# LEDLadderSchem.net
KiCad netlist of a schematic drawn in Altium Designer
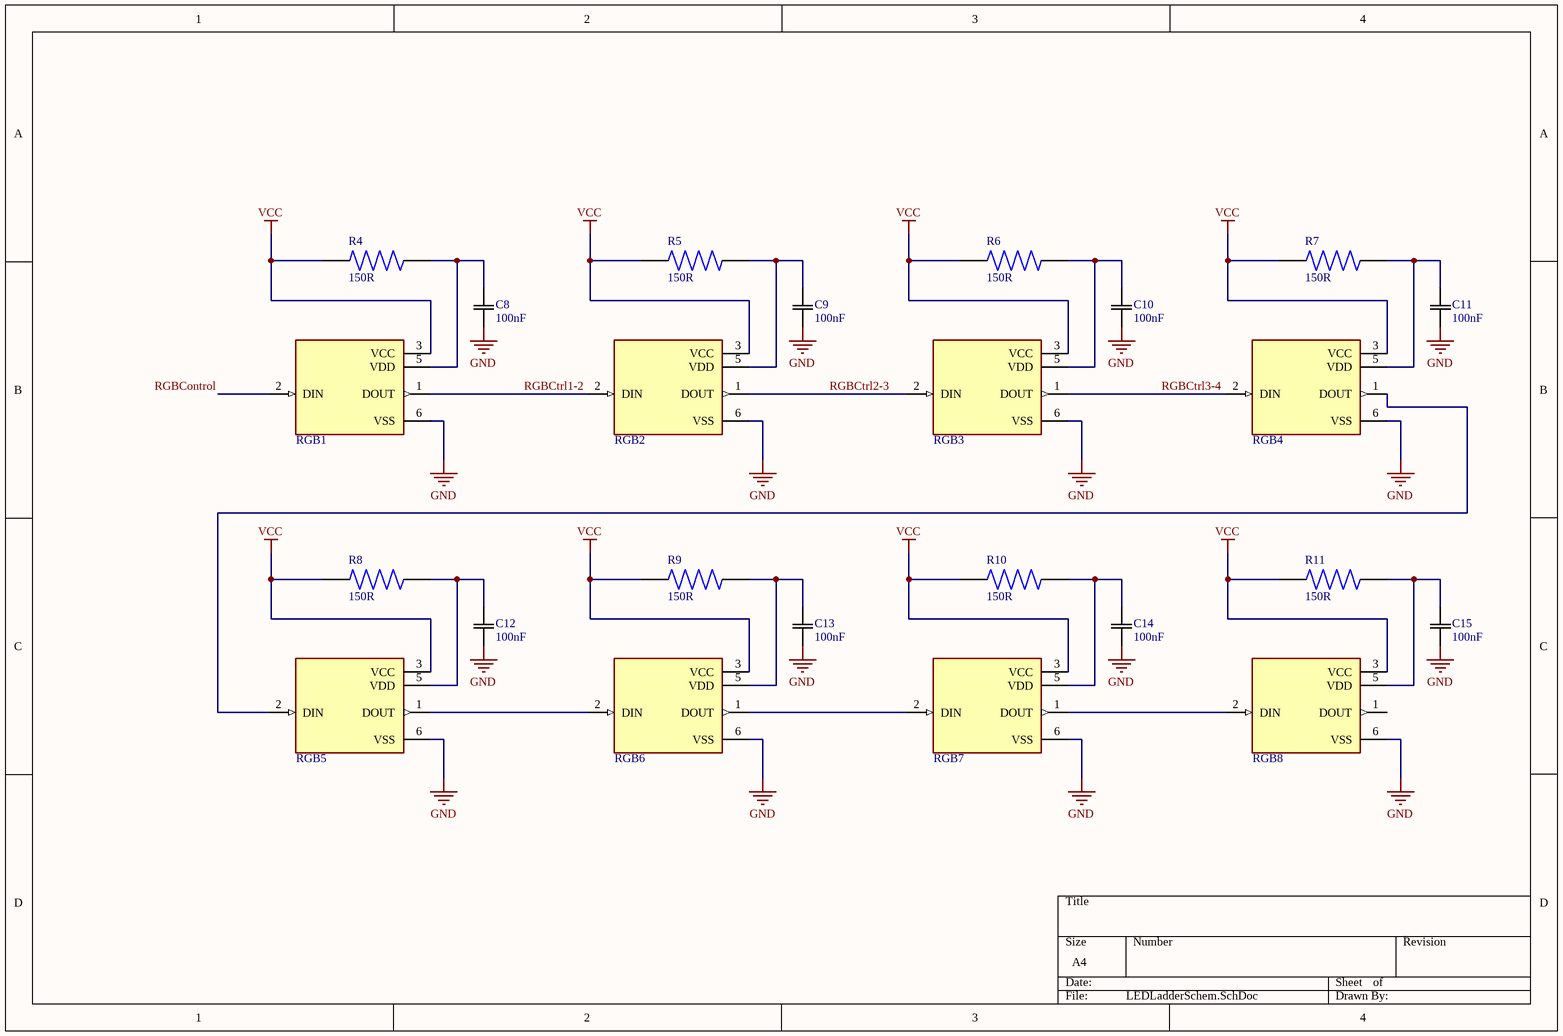
[diagram p0: LEDLadderSchem.SchDoc]

(export (version "E")
  (design (tool "Eeschema 10.0.6"))
  (components
    (comp (ref "C8")
      (value "100nF")
      (footprint "CAPC0603_87N_KEM-M")
      (description "CAP CER 10000PF 50V U2J 0603")
      (fields
        (field (name "MANUFACTURER") "KEMET")
        (field (name "MANUFACTURER PART NUMBER") "C0603C103J5JACTU")
      )
      (libsource (lib "MediaControllerSchLib") (part "C0603C103J5JACTU"))
    )
    (comp (ref "C9")
      (value "100nF")
      (footprint "CAPC0603_87N_KEM-M")
      (description "CAP CER 10000PF 50V U2J 0603")
      (fields
        (field (name "MANUFACTURER") "KEMET")
        (field (name "MANUFACTURER PART NUMBER") "C0603C103J5JACTU")
      )
      (libsource (lib "MediaControllerSchLib") (part "C0603C103J5JACTU"))
    )
    (comp (ref "C10")
      (value "100nF")
      (footprint "CAPC0603_87N_KEM-M")
      (description "CAP CER 10000PF 50V U2J 0603")
      (fields
        (field (name "MANUFACTURER") "KEMET")
        (field (name "MANUFACTURER PART NUMBER") "C0603C103J5JACTU")
      )
      (libsource (lib "MediaControllerSchLib") (part "C0603C103J5JACTU"))
    )
    (comp (ref "C11")
      (value "100nF")
      (footprint "CAPC0603_87N_KEM-M")
      (description "CAP CER 10000PF 50V U2J 0603")
      (fields
        (field (name "MANUFACTURER") "KEMET")
        (field (name "MANUFACTURER PART NUMBER") "C0603C103J5JACTU")
      )
      (libsource (lib "MediaControllerSchLib") (part "C0603C103J5JACTU"))
    )
    (comp (ref "C12")
      (value "100nF")
      (footprint "CAPC0603_87N_KEM-M")
      (description "CAP CER 10000PF 50V U2J 0603")
      (fields
        (field (name "MANUFACTURER") "KEMET")
        (field (name "MANUFACTURER PART NUMBER") "C0603C103J5JACTU")
      )
      (libsource (lib "MediaControllerSchLib") (part "C0603C103J5JACTU"))
    )
    (comp (ref "C13")
      (value "100nF")
      (footprint "CAPC0603_87N_KEM-M")
      (description "CAP CER 10000PF 50V U2J 0603")
      (fields
        (field (name "MANUFACTURER") "KEMET")
        (field (name "MANUFACTURER PART NUMBER") "C0603C103J5JACTU")
      )
      (libsource (lib "MediaControllerSchLib") (part "C0603C103J5JACTU"))
    )
    (comp (ref "C14")
      (value "100nF")
      (footprint "CAPC0603_87N_KEM-M")
      (description "CAP CER 10000PF 50V U2J 0603")
      (fields
        (field (name "MANUFACTURER") "KEMET")
        (field (name "MANUFACTURER PART NUMBER") "C0603C103J5JACTU")
      )
      (libsource (lib "MediaControllerSchLib") (part "C0603C103J5JACTU"))
    )
    (comp (ref "C15")
      (value "100nF")
      (footprint "CAPC0603_87N_KEM-M")
      (description "CAP CER 10000PF 50V U2J 0603")
      (fields
        (field (name "MANUFACTURER") "KEMET")
        (field (name "MANUFACTURER PART NUMBER") "C0603C103J5JACTU")
      )
      (libsource (lib "MediaControllerSchLib") (part "C0603C103J5JACTU"))
    )
    (comp (ref "R4")
      (value "150R")
      (footprint "RES0608_150OHM")
      (description "Res Thick Film 0603 150 Ohm 1% 0.33W(1/3W) ±100ppm/°C Pad SMD Automotive T/R")
      (fields
        (field (name "MANUFACTURER") "Vishay")
        (field (name "MANUFACTURER PART NUMBER") "CRCW0603150RFKEAHP")
      )
      (libsource (lib "MediaControllerSchLib") (part "CRCW0603150RFKEAHP"))
    )
    (comp (ref "R5")
      (value "150R")
      (footprint "RES0608_150OHM")
      (description "Res Thick Film 0603 150 Ohm 1% 0.33W(1/3W) ±100ppm/°C Pad SMD Automotive T/R")
      (fields
        (field (name "MANUFACTURER") "Vishay")
        (field (name "MANUFACTURER PART NUMBER") "CRCW0603150RFKEAHP")
      )
      (libsource (lib "MediaControllerSchLib") (part "CRCW0603150RFKEAHP"))
    )
    (comp (ref "R6")
      (value "150R")
      (footprint "RES0608_150OHM")
      (description "Res Thick Film 0603 150 Ohm 1% 0.33W(1/3W) ±100ppm/°C Pad SMD Automotive T/R")
      (fields
        (field (name "MANUFACTURER") "Vishay")
        (field (name "MANUFACTURER PART NUMBER") "CRCW0603150RFKEAHP")
      )
      (libsource (lib "MediaControllerSchLib") (part "CRCW0603150RFKEAHP"))
    )
    (comp (ref "R7")
      (value "150R")
      (footprint "RES0608_150OHM")
      (description "Res Thick Film 0603 150 Ohm 1% 0.33W(1/3W) ±100ppm/°C Pad SMD Automotive T/R")
      (fields
        (field (name "MANUFACTURER") "Vishay")
        (field (name "MANUFACTURER PART NUMBER") "CRCW0603150RFKEAHP")
      )
      (libsource (lib "MediaControllerSchLib") (part "CRCW0603150RFKEAHP"))
    )
    (comp (ref "R8")
      (value "150R")
      (footprint "RES0608_150OHM")
      (description "Res Thick Film 0603 150 Ohm 1% 0.33W(1/3W) ±100ppm/°C Pad SMD Automotive T/R")
      (fields
        (field (name "MANUFACTURER") "Vishay")
        (field (name "MANUFACTURER PART NUMBER") "CRCW0603150RFKEAHP")
      )
      (libsource (lib "MediaControllerSchLib") (part "CRCW0603150RFKEAHP"))
    )
    (comp (ref "R9")
      (value "150R")
      (footprint "RES0608_150OHM")
      (description "Res Thick Film 0603 150 Ohm 1% 0.33W(1/3W) ±100ppm/°C Pad SMD Automotive T/R")
      (fields
        (field (name "MANUFACTURER") "Vishay")
        (field (name "MANUFACTURER PART NUMBER") "CRCW0603150RFKEAHP")
      )
      (libsource (lib "MediaControllerSchLib") (part "CRCW0603150RFKEAHP"))
    )
    (comp (ref "R10")
      (value "150R")
      (footprint "RES0608_150OHM")
      (description "Res Thick Film 0603 150 Ohm 1% 0.33W(1/3W) ±100ppm/°C Pad SMD Automotive T/R")
      (fields
        (field (name "MANUFACTURER") "Vishay")
        (field (name "MANUFACTURER PART NUMBER") "CRCW0603150RFKEAHP")
      )
      (libsource (lib "MediaControllerSchLib") (part "CRCW0603150RFKEAHP"))
    )
    (comp (ref "R11")
      (value "150R")
      (footprint "RES0608_150OHM")
      (description "Res Thick Film 0603 150 Ohm 1% 0.33W(1/3W) ±100ppm/°C Pad SMD Automotive T/R")
      (fields
        (field (name "MANUFACTURER") "Vishay")
        (field (name "MANUFACTURER PART NUMBER") "CRCW0603150RFKEAHP")
      )
      (libsource (lib "MediaControllerSchLib") (part "CRCW0603150RFKEAHP"))
    )
    (comp (ref "RGB1")
      (value "RGB-LED")
      (footprint "LED_RGB")
      (description "ADDRESS LED DISCRETE SERIAL RGB")
      (fields (field (name "MANUFACTURER") "SparkFun") (field (name "MANUFACTURER PART NUMBER") "COM-11821"))
      (libsource (lib "MediaControllerSchLib") (part "LED_RGB"))
    )
    (comp (ref "RGB2")
      (value "RGB-LED")
      (footprint "LED_RGB")
      (description "ADDRESS LED DISCRETE SERIAL RGB")
      (fields (field (name "MANUFACTURER") "SparkFun") (field (name "MANUFACTURER PART NUMBER") "COM-11821"))
      (libsource (lib "MediaControllerSchLib") (part "LED_RGB"))
    )
    (comp (ref "RGB3")
      (value "RGB-LED")
      (footprint "LED_RGB")
      (description "ADDRESS LED DISCRETE SERIAL RGB")
      (fields (field (name "MANUFACTURER") "SparkFun") (field (name "MANUFACTURER PART NUMBER") "COM-11821"))
      (libsource (lib "MediaControllerSchLib") (part "LED_RGB"))
    )
    (comp (ref "RGB4")
      (value "RGB-LED")
      (footprint "LED_RGB")
      (description "ADDRESS LED DISCRETE SERIAL RGB")
      (fields (field (name "MANUFACTURER") "SparkFun") (field (name "MANUFACTURER PART NUMBER") "COM-11821"))
      (libsource (lib "MediaControllerSchLib") (part "LED_RGB"))
    )
    (comp (ref "RGB5")
      (value "RGB-LED")
      (footprint "LED_RGB")
      (description "ADDRESS LED DISCRETE SERIAL RGB")
      (fields (field (name "MANUFACTURER") "SparkFun") (field (name "MANUFACTURER PART NUMBER") "COM-11821"))
      (libsource (lib "MediaControllerSchLib") (part "LED_RGB"))
    )
    (comp (ref "RGB6")
      (value "RGB-LED")
      (footprint "LED_RGB")
      (description "ADDRESS LED DISCRETE SERIAL RGB")
      (fields (field (name "MANUFACTURER") "SparkFun") (field (name "MANUFACTURER PART NUMBER") "COM-11821"))
      (libsource (lib "MediaControllerSchLib") (part "LED_RGB"))
    )
    (comp (ref "RGB7")
      (value "RGB-LED")
      (footprint "LED_RGB")
      (description "ADDRESS LED DISCRETE SERIAL RGB")
      (fields (field (name "MANUFACTURER") "SparkFun") (field (name "MANUFACTURER PART NUMBER") "COM-11821"))
      (libsource (lib "MediaControllerSchLib") (part "LED_RGB"))
    )
    (comp (ref "RGB8")
      (value "RGB-LED")
      (footprint "LED_RGB")
      (description "ADDRESS LED DISCRETE SERIAL RGB")
      (fields (field (name "MANUFACTURER") "SparkFun") (field (name "MANUFACTURER PART NUMBER") "COM-11821"))
      (libsource (lib "MediaControllerSchLib") (part "LED_RGB"))
    )
  )
  (nets
    (net (code "1") (name "/RGBControl") (class "Default")
      (node (ref "RGB1") (pin "2") (pinfunction "DIN_2") (pintype "input"))
    )
    (net (code "2") (name "/RGBCtrl1-2") (class "Default")
      (node (ref "RGB1") (pin "1") (pinfunction "DOUT_1") (pintype "output"))
      (node (ref "RGB2") (pin "2") (pinfunction "DIN_2") (pintype "input"))
    )
    (net (code "3") (name "/RGBCtrl2-3") (class "Default")
      (node (ref "RGB2") (pin "1") (pinfunction "DOUT_1") (pintype "output"))
      (node (ref "RGB3") (pin "2") (pinfunction "DIN_2") (pintype "input"))
    )
    (net (code "4") (name "/RGBCtrl3-4") (class "Default")
      (node (ref "RGB3") (pin "1") (pinfunction "DOUT_1") (pintype "output"))
      (node (ref "RGB4") (pin "2") (pinfunction "DIN_2") (pintype "input"))
    )
    (net (code "5") (name "GND") (class "Default")
      (node (ref "C10") (pin "1") (pinfunction "1_1") (pintype "passive"))
      (node (ref "C11") (pin "1") (pinfunction "1_1") (pintype "passive"))
      (node (ref "C12") (pin "1") (pinfunction "1_1") (pintype "passive"))
      (node (ref "C13") (pin "1") (pinfunction "1_1") (pintype "passive"))
      (node (ref "C14") (pin "1") (pinfunction "1_1") (pintype "passive"))
      (node (ref "C15") (pin "1") (pinfunction "1_1") (pintype "passive"))
      (node (ref "C8") (pin "1") (pinfunction "1_1") (pintype "passive"))
      (node (ref "C9") (pin "1") (pinfunction "1_1") (pintype "passive"))
      (node (ref "RGB1") (pin "6") (pinfunction "VSS_6") (pintype "power_in"))
      (node (ref "RGB2") (pin "6") (pinfunction "VSS_6") (pintype "power_in"))
      (node (ref "RGB3") (pin "6") (pinfunction "VSS_6") (pintype "power_in"))
      (node (ref "RGB4") (pin "6") (pinfunction "VSS_6") (pintype "power_in"))
      (node (ref "RGB5") (pin "6") (pinfunction "VSS_6") (pintype "power_in"))
      (node (ref "RGB6") (pin "6") (pinfunction "VSS_6") (pintype "power_in"))
      (node (ref "RGB7") (pin "6") (pinfunction "VSS_6") (pintype "power_in"))
      (node (ref "RGB8") (pin "6") (pinfunction "VSS_6") (pintype "power_in"))
    )
    (net (code "6") (name "Net-(RGB1-VDD)") (class "Default")
      (node (ref "C8") (pin "2") (pinfunction "2_2") (pintype "passive"))
      (node (ref "R4") (pin "2") (pinfunction "2_2") (pintype "passive"))
      (node (ref "RGB1") (pin "5") (pinfunction "VDD_5") (pintype "power_in"))
    )
    (net (code "7") (name "Net-(RGB2-VDD)") (class "Default")
      (node (ref "C9") (pin "2") (pinfunction "2_2") (pintype "passive"))
      (node (ref "R5") (pin "2") (pinfunction "2_2") (pintype "passive"))
      (node (ref "RGB2") (pin "5") (pinfunction "VDD_5") (pintype "power_in"))
    )
    (net (code "8") (name "Net-(RGB3-VDD)") (class "Default")
      (node (ref "C10") (pin "2") (pinfunction "2_2") (pintype "passive"))
      (node (ref "R6") (pin "2") (pinfunction "2_2") (pintype "passive"))
      (node (ref "RGB3") (pin "5") (pinfunction "VDD_5") (pintype "power_in"))
    )
    (net (code "9") (name "Net-(RGB4-DOUT)") (class "Default")
      (node (ref "RGB4") (pin "1") (pinfunction "DOUT_1") (pintype "output"))
      (node (ref "RGB5") (pin "2") (pinfunction "DIN_2") (pintype "input"))
    )
    (net (code "10") (name "Net-(RGB4-VDD)") (class "Default")
      (node (ref "C11") (pin "2") (pinfunction "2_2") (pintype "passive"))
      (node (ref "R7") (pin "2") (pinfunction "2_2") (pintype "passive"))
      (node (ref "RGB4") (pin "5") (pinfunction "VDD_5") (pintype "power_in"))
    )
    (net (code "11") (name "Net-(RGB5-DOUT)") (class "Default")
      (node (ref "RGB5") (pin "1") (pinfunction "DOUT_1") (pintype "output"))
      (node (ref "RGB6") (pin "2") (pinfunction "DIN_2") (pintype "input"))
    )
    (net (code "12") (name "Net-(RGB5-VDD)") (class "Default")
      (node (ref "C12") (pin "2") (pinfunction "2_2") (pintype "passive"))
      (node (ref "R8") (pin "2") (pinfunction "2_2") (pintype "passive"))
      (node (ref "RGB5") (pin "5") (pinfunction "VDD_5") (pintype "power_in"))
    )
    (net (code "13") (name "Net-(RGB6-DOUT)") (class "Default")
      (node (ref "RGB6") (pin "1") (pinfunction "DOUT_1") (pintype "output"))
      (node (ref "RGB7") (pin "2") (pinfunction "DIN_2") (pintype "input"))
    )
    (net (code "14") (name "Net-(RGB6-VDD)") (class "Default")
      (node (ref "C13") (pin "2") (pinfunction "2_2") (pintype "passive"))
      (node (ref "R9") (pin "2") (pinfunction "2_2") (pintype "passive"))
      (node (ref "RGB6") (pin "5") (pinfunction "VDD_5") (pintype "power_in"))
    )
    (net (code "15") (name "Net-(RGB7-DOUT)") (class "Default")
      (node (ref "RGB7") (pin "1") (pinfunction "DOUT_1") (pintype "output"))
      (node (ref "RGB8") (pin "2") (pinfunction "DIN_2") (pintype "input"))
    )
    (net (code "16") (name "Net-(RGB7-VDD)") (class "Default")
      (node (ref "C14") (pin "2") (pinfunction "2_2") (pintype "passive"))
      (node (ref "R10") (pin "2") (pinfunction "2_2") (pintype "passive"))
      (node (ref "RGB7") (pin "5") (pinfunction "VDD_5") (pintype "power_in"))
    )
    (net (code "17") (name "Net-(RGB8-VDD)") (class "Default")
      (node (ref "C15") (pin "2") (pinfunction "2_2") (pintype "passive"))
      (node (ref "R11") (pin "2") (pinfunction "2_2") (pintype "passive"))
      (node (ref "RGB8") (pin "5") (pinfunction "VDD_5") (pintype "power_in"))
    )
    (net (code "18") (name "VCC") (class "Default")
      (node (ref "R10") (pin "1") (pinfunction "1_1") (pintype "passive"))
      (node (ref "R11") (pin "1") (pinfunction "1_1") (pintype "passive"))
      (node (ref "R4") (pin "1") (pinfunction "1_1") (pintype "passive"))
      (node (ref "R5") (pin "1") (pinfunction "1_1") (pintype "passive"))
      (node (ref "R6") (pin "1") (pinfunction "1_1") (pintype "passive"))
      (node (ref "R7") (pin "1") (pinfunction "1_1") (pintype "passive"))
      (node (ref "R8") (pin "1") (pinfunction "1_1") (pintype "passive"))
      (node (ref "R9") (pin "1") (pinfunction "1_1") (pintype "passive"))
      (node (ref "RGB1") (pin "3") (pinfunction "VCC_3") (pintype "power_in"))
      (node (ref "RGB2") (pin "3") (pinfunction "VCC_3") (pintype "power_in"))
      (node (ref "RGB3") (pin "3") (pinfunction "VCC_3") (pintype "power_in"))
      (node (ref "RGB4") (pin "3") (pinfunction "VCC_3") (pintype "power_in"))
      (node (ref "RGB5") (pin "3") (pinfunction "VCC_3") (pintype "power_in"))
      (node (ref "RGB6") (pin "3") (pinfunction "VCC_3") (pintype "power_in"))
      (node (ref "RGB7") (pin "3") (pinfunction "VCC_3") (pintype "power_in"))
      (node (ref "RGB8") (pin "3") (pinfunction "VCC_3") (pintype "power_in"))
    )
    (net (code "19") (name "unconnected-(RGB8-DOUT-Pad1)") (class "Default")
      (node (ref "RGB8") (pin "1") (pinfunction "DOUT_1") (pintype "output"))
    )
  )
)
